# Sheet1.net
KiCad netlist of a schematic drawn in Altium Designer
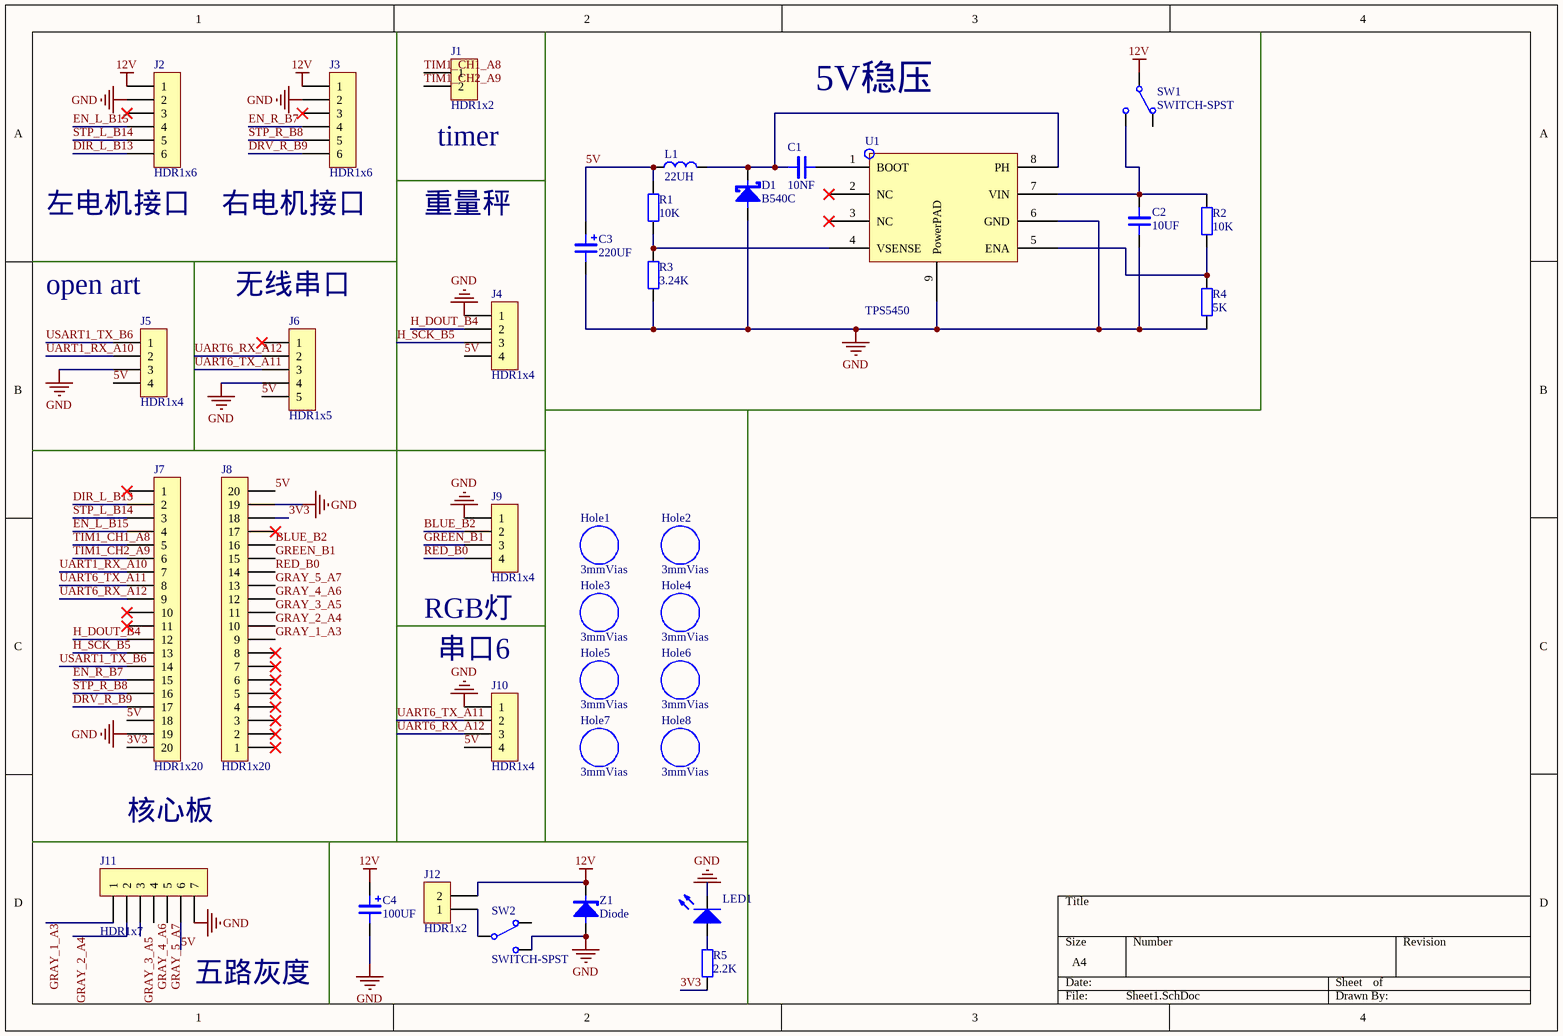
[diagram p0: Sheet1.SchDoc]

(export (version "E")
  (design (tool "Eeschema 10.0.6"))
  (components
    (comp (ref "C1")
      (value "10NF")
      (footprint "0603")
      (description "Capacitor")
      (libsource (lib "General") (part "CAP"))
    )
    (comp (ref "C2")
      (value "10UF")
      (footprint "0603")
      (description "Capacitor")
      (libsource (lib "General") (part "CAP"))
    )
    (comp (ref "C3")
      (value "220UF")
      (footprint "DIP-EC3.5X8X11.5")
      (description "Tantalum Capacitor")
      (libsource (lib "General") (part "CAP-TANTALUM"))
    )
    (comp (ref "C4")
      (value "100UF")
      (footprint "DIP-EC2.5X6.3X11.2")
      (description "Tantalum Capacitor")
      (libsource (lib "General") (part "CAP-TANTALUM"))
    )
    (comp (ref "D1")
      (value "B540C")
      (footprint "SMC")
      (description "Schottky Diode")
      (libsource (lib "General") (part "SS5x"))
    )
    (comp (ref "Hole1") (value "3mmVias") (footprint "3mm") (libsource (lib "General") (part "3mmVias")))
    (comp (ref "Hole2") (value "3mmVias") (footprint "3mm") (libsource (lib "General") (part "3mmVias")))
    (comp (ref "Hole3") (value "3mmVias") (footprint "3mm") (libsource (lib "General") (part "3mmVias")))
    (comp (ref "Hole4") (value "3mmVias") (footprint "3mm") (libsource (lib "General") (part "3mmVias")))
    (comp (ref "Hole5") (value "3mmVias") (footprint "3mm") (libsource (lib "General") (part "3mmVias")))
    (comp (ref "Hole6") (value "3mmVias") (footprint "3mm") (libsource (lib "General") (part "3mmVias")))
    (comp (ref "Hole7") (value "3mmVias") (footprint "3mm") (libsource (lib "General") (part "3mmVias")))
    (comp (ref "Hole8") (value "3mmVias") (footprint "3mm") (libsource (lib "General") (part "3mmVias")))
    (comp (ref "J1")
      (value "HDR1x2")
      (footprint "PIN-2-2.54-1.0")
      (description "Connector")
      (libsource (lib "General") (part "HDR1x2"))
    )
    (comp (ref "J2")
      (value "HDR1x6")
      (footprint "XH6/2.54mm/90")
      (description "Connector")
      (libsource (lib "General") (part "HDR1x6"))
    )
    (comp (ref "J3")
      (value "HDR1x6")
      (footprint "XH6/2.54mm/90")
      (description "Connector")
      (libsource (lib "General") (part "HDR1x6"))
    )
    (comp (ref "J4")
      (value "HDR1x4")
      (footprint "PIN-4-2.54-1.0")
      (description "Connector")
      (libsource (lib "General") (part "HDR1x4"))
    )
    (comp (ref "J5")
      (value "HDR1x4")
      (footprint "XH4/2.54mm/180")
      (description "Connector")
      (libsource (lib "General") (part "HDR1x4"))
    )
    (comp (ref "J6")
      (value "HDR1x5")
      (footprint "PIN-5-2.54-1.0")
      (description "Connector")
      (libsource (lib "General") (part "HDR1x5"))
    )
    (comp (ref "J7")
      (value "HDR1x20")
      (footprint "Fe-HDR1X20/2.54-S")
      (description "Connector")
      (libsource (lib "General") (part "HDR1x20"))
    )
    (comp (ref "J8")
      (value "HDR1x20")
      (footprint "Fe-HDR1X20/2.54-S")
      (description "Connector")
      (libsource (lib "") (part "HDR1x20_1"))
    )
    (comp (ref "J9")
      (value "HDR1x4")
      (footprint "PIN-4-2.54-1.0")
      (description "Connector")
      (libsource (lib "General") (part "HDR1x4"))
    )
    (comp (ref "J10")
      (value "HDR1x4")
      (footprint "XH4/2.54mm/180")
      (description "Connector")
      (libsource (lib "General") (part "HDR1x4"))
    )
    (comp (ref "J11")
      (value "HDR1x7")
      (footprint "PIN-7-2.54-1.0")
      (description "Connector")
      (libsource (lib "General") (part "HDR1x7"))
    )
    (comp (ref "J12")
      (value "HDR1x2")
      (footprint "KF301")
      (description "Connector")
      (libsource (lib "") (part "HDR1x2_1"))
    )
    (comp (ref "L1")
      (value "22UH")
      (footprint "CDRH127")
      (description "Inductance")
      (libsource (lib "General") (part "INDUCTANCE"))
    )
    (comp (ref "LED1")
      (value "LED0")
      (footprint "0603-led")
      (description "Typical INFRARED GaAs LED")
      (fields (field (name "PUBLISHER") "Altium Limited"))
      (libsource (lib "Miscellaneous Devices") (part "LED0"))
    )
    (comp (ref "R1")
      (value "10K")
      (footprint "0603")
      (description "Resistor")
      (libsource (lib "General") (part "RES"))
    )
    (comp (ref "R2")
      (value "10K")
      (footprint "0603")
      (description "Resistor")
      (libsource (lib "General") (part "RES"))
    )
    (comp (ref "R3")
      (value "3.24K")
      (footprint "0603")
      (description "Resistor")
      (libsource (lib "General") (part "RES"))
    )
    (comp (ref "R4")
      (value "5K")
      (footprint "0603")
      (description "Resistor")
      (libsource (lib "General") (part "RES"))
    )
    (comp (ref "R5")
      (value "2.2K")
      (footprint "0603")
      (description "Resistor")
      (libsource (lib "General") (part "RES"))
    )
    (comp (ref "SW1")
      (value "SWITCH-SPST")
      (footprint "ss12d10")
      (description "Switch")
      (libsource (lib "General") (part "SWITCH-SPST"))
    )
    (comp (ref "SW2")
      (value "SWITCH-SPST")
      (footprint "ss12d10")
      (description "Switch")
      (libsource (lib "General") (part "SWITCH-SPST"))
    )
    (comp (ref "U1") (value "TPS5450") (footprint "TPS5450") (libsource (lib "General") (part "TPS5450")))
    (comp (ref "Z1")
      (value "Diode")
      (footprint "1N5824")
      (description "Zener Diode")
      (libsource (lib "General") (part "Diode"))
    )
  )
  (nets
    (net (code "1") (name "/3V3") (class "Default")
      (node (ref "J7") (pin "20") (pinfunction "20_20") (pintype "passive"))
      (node (ref "J8") (pin "18") (pinfunction "18_18") (pintype "passive"))
      (node (ref "R5") (pin "1") (pinfunction "1_1") (pintype "passive"))
    )
    (net (code "2") (name "/5V") (class "Default")
      (node (ref "C3") (pin "1") (pinfunction "1_1") (pintype "passive"))
      (node (ref "J10") (pin "4") (pinfunction "4_4") (pintype "passive"))
      (node (ref "J11") (pin "6") (pinfunction "6_6") (pintype "passive"))
      (node (ref "J4") (pin "4") (pinfunction "4_4") (pintype "passive"))
      (node (ref "J5") (pin "4") (pinfunction "4_4") (pintype "passive"))
      (node (ref "J6") (pin "5") (pinfunction "5_5") (pintype "passive"))
      (node (ref "J7") (pin "18") (pinfunction "18_18") (pintype "passive"))
      (node (ref "J8") (pin "20") (pinfunction "20_20") (pintype "passive"))
      (node (ref "L1") (pin "1") (pinfunction "1_1") (pintype "passive"))
      (node (ref "R1") (pin "2") (pinfunction "2_2") (pintype "passive"))
    )
    (net (code "3") (name "/BLUE_B2") (class "Default")
      (node (ref "J8") (pin "16") (pinfunction "16_16") (pintype "passive"))
      (node (ref "J9") (pin "2") (pinfunction "2_2") (pintype "passive"))
    )
    (net (code "4") (name "/DIR_L_B13") (class "Default")
      (node (ref "J2") (pin "6") (pinfunction "6_6") (pintype "passive"))
      (node (ref "J7") (pin "2") (pinfunction "2_2") (pintype "passive"))
    )
    (net (code "5") (name "/DRV_R_B9") (class "Default")
      (node (ref "J3") (pin "6") (pinfunction "6_6") (pintype "passive"))
      (node (ref "J7") (pin "17") (pinfunction "17_17") (pintype "passive"))
    )
    (net (code "6") (name "/EN_L_B15") (class "Default")
      (node (ref "J2") (pin "4") (pinfunction "4_4") (pintype "passive"))
      (node (ref "J7") (pin "4") (pinfunction "4_4") (pintype "passive"))
    )
    (net (code "7") (name "/EN_R_B7") (class "Default")
      (node (ref "J3") (pin "4") (pinfunction "4_4") (pintype "passive"))
      (node (ref "J7") (pin "15") (pinfunction "15_15") (pintype "passive"))
    )
    (net (code "8") (name "/GRAY_1_A3") (class "Default")
      (node (ref "J11") (pin "1") (pinfunction "1_1") (pintype "passive"))
      (node (ref "J8") (pin "9") (pinfunction "9_9") (pintype "passive"))
    )
    (net (code "9") (name "/GRAY_2_A4") (class "Default")
      (node (ref "J11") (pin "2") (pinfunction "2_2") (pintype "passive"))
      (node (ref "J8") (pin "10") (pinfunction "10_10") (pintype "passive"))
    )
    (net (code "10") (name "/GRAY_3_A5") (class "Default")
      (node (ref "J11") (pin "3") (pinfunction "3_3") (pintype "passive"))
      (node (ref "J8") (pin "11") (pinfunction "11_11") (pintype "passive"))
    )
    (net (code "11") (name "/GRAY_4_A6") (class "Default")
      (node (ref "J11") (pin "4") (pinfunction "4_4") (pintype "passive"))
      (node (ref "J8") (pin "12") (pinfunction "12_12") (pintype "passive"))
    )
    (net (code "12") (name "/GRAY_5_A7") (class "Default")
      (node (ref "J11") (pin "5") (pinfunction "5_5") (pintype "passive"))
      (node (ref "J8") (pin "13") (pinfunction "13_13") (pintype "passive"))
    )
    (net (code "13") (name "/GREEN_B1") (class "Default")
      (node (ref "J8") (pin "15") (pinfunction "15_15") (pintype "passive"))
      (node (ref "J9") (pin "3") (pinfunction "3_3") (pintype "passive"))
    )
    (net (code "14") (name "/H_DOUT_B4") (class "Default")
      (node (ref "J4") (pin "2") (pinfunction "2_2") (pintype "passive"))
      (node (ref "J7") (pin "12") (pinfunction "12_12") (pintype "passive"))
    )
    (net (code "15") (name "/H_SCK_B5") (class "Default")
      (node (ref "J4") (pin "3") (pinfunction "3_3") (pintype "passive"))
      (node (ref "J7") (pin "13") (pinfunction "13_13") (pintype "passive"))
    )
    (net (code "16") (name "/RED_B0") (class "Default")
      (node (ref "J8") (pin "14") (pinfunction "14_14") (pintype "passive"))
      (node (ref "J9") (pin "4") (pinfunction "4_4") (pintype "passive"))
    )
    (net (code "17") (name "/STP_L_B14") (class "Default")
      (node (ref "J2") (pin "5") (pinfunction "5_5") (pintype "passive"))
      (node (ref "J7") (pin "3") (pinfunction "3_3") (pintype "passive"))
    )
    (net (code "18") (name "/STP_R_B8") (class "Default")
      (node (ref "J3") (pin "5") (pinfunction "5_5") (pintype "passive"))
      (node (ref "J7") (pin "16") (pinfunction "16_16") (pintype "passive"))
    )
    (net (code "19") (name "/TIM1_CH1_A8") (class "Default")
      (node (ref "J1") (pin "1") (pinfunction "1_1") (pintype "passive"))
      (node (ref "J7") (pin "5") (pinfunction "5_5") (pintype "passive"))
    )
    (net (code "20") (name "/TIM1_CH2_A9") (class "Default")
      (node (ref "J1") (pin "2") (pinfunction "2_2") (pintype "passive"))
      (node (ref "J7") (pin "6") (pinfunction "6_6") (pintype "passive"))
    )
    (net (code "21") (name "/UART1_RX_A10") (class "Default")
      (node (ref "J5") (pin "2") (pinfunction "2_2") (pintype "passive"))
      (node (ref "J7") (pin "7") (pinfunction "7_7") (pintype "passive"))
    )
    (net (code "22") (name "/UART6_RX_A12") (class "Default")
      (node (ref "J10") (pin "3") (pinfunction "3_3") (pintype "passive"))
      (node (ref "J6") (pin "2") (pinfunction "2_2") (pintype "passive"))
      (node (ref "J7") (pin "9") (pinfunction "9_9") (pintype "passive"))
    )
    (net (code "23") (name "/UART6_TX_A11") (class "Default")
      (node (ref "J10") (pin "2") (pinfunction "2_2") (pintype "passive"))
      (node (ref "J6") (pin "3") (pinfunction "3_3") (pintype "passive"))
      (node (ref "J7") (pin "8") (pinfunction "8_8") (pintype "passive"))
    )
    (net (code "24") (name "/USART1_TX_B6") (class "Default")
      (node (ref "J5") (pin "1") (pinfunction "1_1") (pintype "passive"))
      (node (ref "J7") (pin "14") (pinfunction "14_14") (pintype "passive"))
    )
    (net (code "25") (name "12V") (class "Default")
      (node (ref "C4") (pin "1") (pinfunction "1_1") (pintype "passive"))
      (node (ref "J12") (pin "2") (pinfunction "2_2") (pintype "passive"))
      (node (ref "J2") (pin "1") (pinfunction "1_1") (pintype "passive"))
      (node (ref "J3") (pin "1") (pinfunction "1_1") (pintype "passive"))
      (node (ref "SW1") (pin "2") (pinfunction "2_2") (pintype "passive"))
      (node (ref "Z1") (pin "2") (pinfunction "C_2") (pintype "passive"))
    )
    (net (code "26") (name "GND") (class "Default")
      (node (ref "C2") (pin "1") (pinfunction "1_1") (pintype "passive"))
      (node (ref "C3") (pin "2") (pinfunction "2_2") (pintype "passive"))
      (node (ref "C4") (pin "2") (pinfunction "2_2") (pintype "passive"))
      (node (ref "D1") (pin "1") (pinfunction "A_1") (pintype "passive"))
      (node (ref "J10") (pin "1") (pinfunction "1_1") (pintype "passive"))
      (node (ref "J11") (pin "7") (pinfunction "7_7") (pintype "passive"))
      (node (ref "J2") (pin "2") (pinfunction "2_2") (pintype "passive"))
      (node (ref "J3") (pin "2") (pinfunction "2_2") (pintype "passive"))
      (node (ref "J4") (pin "1") (pinfunction "1_1") (pintype "passive"))
      (node (ref "J5") (pin "3") (pinfunction "3_3") (pintype "passive"))
      (node (ref "J6") (pin "4") (pinfunction "4_4") (pintype "passive"))
      (node (ref "J7") (pin "19") (pinfunction "19_19") (pintype "passive"))
      (node (ref "J8") (pin "19") (pinfunction "19_19") (pintype "passive"))
      (node (ref "J9") (pin "1") (pinfunction "1_1") (pintype "passive"))
      (node (ref "LED1") (pin "2") (pinfunction "K_2") (pintype "passive"))
      (node (ref "R3") (pin "1") (pinfunction "1_1") (pintype "passive"))
      (node (ref "R4") (pin "1") (pinfunction "1_1") (pintype "passive"))
      (node (ref "SW2") (pin "3") (pinfunction "3_3") (pintype "passive"))
      (node (ref "U1") (pin "6") (pinfunction "GND_6") (pintype "passive"))
      (node (ref "U1") (pin "9") (pinfunction "PowerPAD_9") (pintype "passive"))
      (node (ref "Z1") (pin "1") (pinfunction "A_1") (pintype "passive"))
    )
    (net (code "27") (name "Net-(D1-C)") (class "Default")
      (node (ref "C1") (pin "2") (pinfunction "2_2") (pintype "passive"))
      (node (ref "D1") (pin "2") (pinfunction "C_2") (pintype "passive"))
      (node (ref "L1") (pin "2") (pinfunction "2_2") (pintype "passive"))
      (node (ref "U1") (pin "8") (pinfunction "PH_8") (pintype "passive"))
    )
    (net (code "28") (name "Net-(J12-Pad1)") (class "Default")
      (node (ref "J12") (pin "1") (pinfunction "1_1") (pintype "passive"))
      (node (ref "SW2") (pin "2") (pinfunction "2_2") (pintype "passive"))
    )
    (net (code "29") (name "Net-(LED1-A)") (class "Default")
      (node (ref "LED1") (pin "1") (pinfunction "A_1") (pintype "passive"))
      (node (ref "R5") (pin "2") (pinfunction "2_2") (pintype "passive"))
    )
    (net (code "30") (name "Net-(U1-BOOT)") (class "Default")
      (node (ref "C1") (pin "1") (pinfunction "1_1") (pintype "passive"))
      (node (ref "U1") (pin "1") (pinfunction "BOOT_1") (pintype "passive"))
    )
    (net (code "31") (name "Net-(U1-ENA)") (class "Default")
      (node (ref "R2") (pin "1") (pinfunction "1_1") (pintype "passive"))
      (node (ref "R4") (pin "2") (pinfunction "2_2") (pintype "passive"))
      (node (ref "U1") (pin "5") (pinfunction "ENA_5") (pintype "passive"))
    )
    (net (code "32") (name "Net-(U1-VIN)") (class "Default")
      (node (ref "C2") (pin "2") (pinfunction "2_2") (pintype "passive"))
      (node (ref "R2") (pin "2") (pinfunction "2_2") (pintype "passive"))
      (node (ref "SW1") (pin "3") (pinfunction "3_3") (pintype "passive"))
      (node (ref "U1") (pin "7") (pinfunction "VIN_7") (pintype "passive"))
    )
    (net (code "33") (name "Net-(U1-VSENSE)") (class "Default")
      (node (ref "R1") (pin "1") (pinfunction "1_1") (pintype "passive"))
      (node (ref "R3") (pin "2") (pinfunction "2_2") (pintype "passive"))
      (node (ref "U1") (pin "4") (pinfunction "VSENSE_4") (pintype "passive"))
    )
    (net (code "34") (name "unconnected-(J2-Pad3)") (class "Default")
      (node (ref "J2") (pin "3") (pinfunction "3_3") (pintype "passive+no_connect"))
    )
    (net (code "35") (name "unconnected-(J3-Pad3)") (class "Default")
      (node (ref "J3") (pin "3") (pinfunction "3_3") (pintype "passive+no_connect"))
    )
    (net (code "36") (name "unconnected-(J6-Pad1)") (class "Default")
      (node (ref "J6") (pin "1") (pinfunction "1_1") (pintype "passive+no_connect"))
    )
    (net (code "37") (name "unconnected-(J7-Pad1)") (class "Default")
      (node (ref "J7") (pin "1") (pinfunction "1_1") (pintype "passive+no_connect"))
    )
    (net (code "38") (name "unconnected-(J7-Pad10)") (class "Default")
      (node (ref "J7") (pin "10") (pinfunction "10_10") (pintype "passive+no_connect"))
    )
    (net (code "39") (name "unconnected-(J7-Pad11)") (class "Default")
      (node (ref "J7") (pin "11") (pinfunction "11_11") (pintype "passive+no_connect"))
    )
    (net (code "40") (name "unconnected-(J8-Pad1)") (class "Default")
      (node (ref "J8") (pin "1") (pinfunction "1_1") (pintype "passive+no_connect"))
    )
    (net (code "41") (name "unconnected-(J8-Pad2)") (class "Default")
      (node (ref "J8") (pin "2") (pinfunction "2_2") (pintype "passive+no_connect"))
    )
    (net (code "42") (name "unconnected-(J8-Pad3)") (class "Default")
      (node (ref "J8") (pin "3") (pinfunction "3_3") (pintype "passive+no_connect"))
    )
    (net (code "43") (name "unconnected-(J8-Pad4)") (class "Default")
      (node (ref "J8") (pin "4") (pinfunction "4_4") (pintype "passive+no_connect"))
    )
    (net (code "44") (name "unconnected-(J8-Pad5)") (class "Default")
      (node (ref "J8") (pin "5") (pinfunction "5_5") (pintype "passive+no_connect"))
    )
    (net (code "45") (name "unconnected-(J8-Pad6)") (class "Default")
      (node (ref "J8") (pin "6") (pinfunction "6_6") (pintype "passive+no_connect"))
    )
    (net (code "46") (name "unconnected-(J8-Pad7)") (class "Default")
      (node (ref "J8") (pin "7") (pinfunction "7_7") (pintype "passive+no_connect"))
    )
    (net (code "47") (name "unconnected-(J8-Pad8)") (class "Default")
      (node (ref "J8") (pin "8") (pinfunction "8_8") (pintype "passive+no_connect"))
    )
    (net (code "48") (name "unconnected-(J8-Pad17)") (class "Default")
      (node (ref "J8") (pin "17") (pinfunction "17_17") (pintype "passive+no_connect"))
    )
    (net (code "49") (name "unconnected-(SW1-Pad1)") (class "Default")
      (node (ref "SW1") (pin "1") (pinfunction "1_1") (pintype "passive"))
    )
    (net (code "50") (name "unconnected-(SW2-Pad1)") (class "Default")
      (node (ref "SW2") (pin "1") (pinfunction "1_1") (pintype "passive"))
    )
    (net (code "51") (name "unconnected-(U1-NC-Pad2)") (class "Default")
      (node (ref "U1") (pin "2") (pinfunction "NC_2") (pintype "passive+no_connect"))
    )
    (net (code "52") (name "unconnected-(U1-NC-Pad3)") (class "Default")
      (node (ref "U1") (pin "3") (pinfunction "NC_3") (pintype "passive+no_connect"))
    )
  )
)
